# STM32F103_coreboard_2.net
KiCad netlist of a schematic drawn in Altium Designer
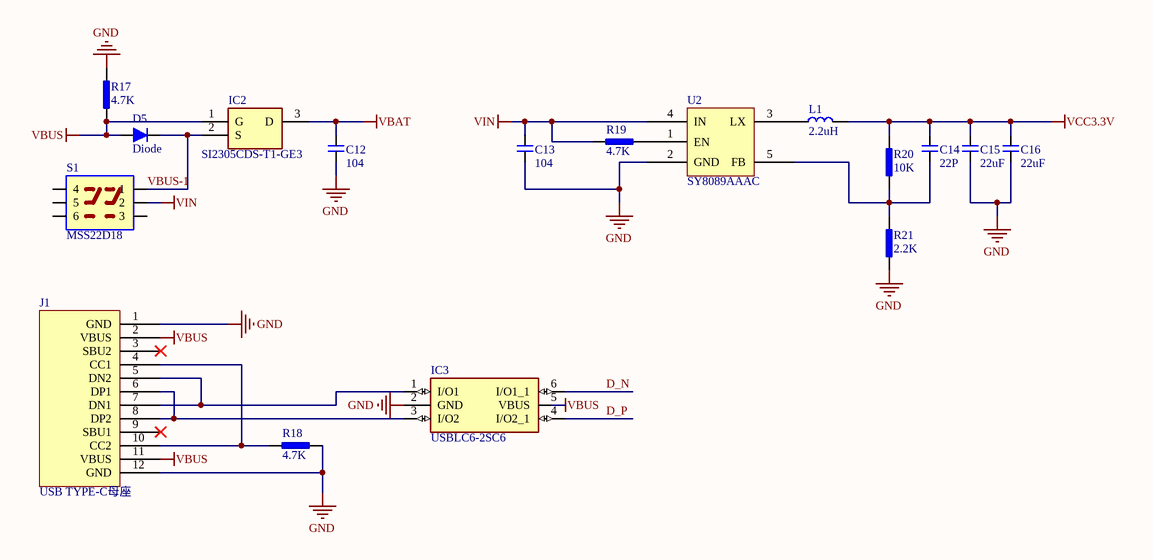
[diagram p0: STM32F103_coreboard_2.SchDoc]

(export (version "E")
  (design (tool "Eeschema 10.0.6"))
  (components
    (comp (ref "C12")
      (value "104")
      (footprint "C0603")
      (description "Cap")
      (libsource (lib "SCH_Bacsic") (part "CAP"))
    )
    (comp (ref "C13")
      (value "104")
      (footprint "C0603")
      (description "Cap")
      (libsource (lib "SCH_Bacsic") (part "CAP"))
    )
    (comp (ref "C14")
      (value "22P")
      (footprint "C0603")
      (description "Cap")
      (libsource (lib "SCH_Bacsic") (part "CAP"))
    )
    (comp (ref "C15")
      (value "22uF")
      (footprint "C0603")
      (description "Cap")
      (libsource (lib "SCH_Bacsic") (part "CAP"))
    )
    (comp (ref "C16")
      (value "22uF")
      (footprint "C0603")
      (description "Cap")
      (libsource (lib "SCH_Bacsic") (part "CAP"))
    )
    (comp (ref "D5") (value "Diode") (footprint "SOD123") (libsource (lib "SCH_Bacsic") (part "Diode")))
    (comp (ref "IC2")
      (value "SI2305CDS-T1-GE3")
      (footprint "SamacSys:SOT95P237X112-3N")
      (description "Integrated Circuit")
      (fields
        (field (name "MOUSER PART NUMBER") "781-SI2305CDS-GE3")
        (field (name "RS PART NUMBER") "7103248P")
      )
      (libsource (lib "*") (part "SI2305CDS-T1-GE3"))
    )
    (comp (ref "IC3")
      (value "USBLC6-2SC6")
      (footprint "SamacSys:SOT95P280X145-6N")
      (description "Integrated Circuit")
      (fields
        (field (name "MOUSER PART NUMBER") "511-USBLC6-2SC6")
        (field (name "RS PART NUMBER") "6247693P")
      )
      (libsource (lib "*") (part "USBLC6-2SC6"))
    )
    (comp (ref "J1")
      (value "USB TYPE-C母座")
      (footprint "USB-TYPEC-SMT")
      (libsource (lib "SCH_Connector") (part "USB TYPE-C"))
    )
    (comp (ref "L1")
      (value "2.2uH")
      (footprint "L-CDR5*5")
      (libsource (lib "SCH_Bacsic") (part "Inductance"))
    )
    (comp (ref "R17") (value "4.7K") (footprint "R0603") (libsource (lib "") (part "RES_2")))
    (comp (ref "R18") (value "4.7K") (footprint "R0603") (libsource (lib "SCH_Bacsic") (part "RES")))
    (comp (ref "R19") (value "4.7K") (footprint "R0603") (libsource (lib "SCH_Bacsic") (part "RES")))
    (comp (ref "R20") (value "10K") (footprint "R0603") (libsource (lib "") (part "RES_1")))
    (comp (ref "R21") (value "2.2K") (footprint "R0603") (libsource (lib "") (part "RES_1")))
    (comp (ref "S1")
      (value "MSS22D18")
      (footprint "SWITCH-MSS22D18")
      (libsource (lib "SCH_Switch_and_Key") (part "SWITCH-MSS22D18"))
    )
    (comp (ref "U2")
      (value "SY8089AAAC")
      (footprint "SOT-23-5")
      (libsource (lib "SCH_Integrated_Circuit") (part "SY8089AAAC"))
    )
  )
  (nets
    (net (code "1") (name "/D_N") (class "Default")
      (node (ref "IC3") (pin "6") (pinfunction "I/O1_1_6") (pintype "bidirectional"))
    )
    (net (code "2") (name "/D_P") (class "Default")
      (node (ref "IC3") (pin "4") (pinfunction "I/O2_1_4") (pintype "bidirectional"))
    )
    (net (code "3") (name "/VBUS-1") (class "Default")
      (node (ref "D5") (pin "2") (pintype "passive"))
      (node (ref "IC2") (pin "2") (pinfunction "S_2") (pintype "passive"))
      (node (ref "S1") (pin "1") (pinfunction "1_1") (pintype "passive"))
    )
    (net (code "4") (name "GND") (class "Default")
      (node (ref "C12") (pin "1") (pintype "passive"))
      (node (ref "C13") (pin "1") (pintype "passive"))
      (node (ref "C15") (pin "1") (pintype "passive"))
      (node (ref "C16") (pin "1") (pintype "passive"))
      (node (ref "IC3") (pin "2") (pinfunction "GND_2") (pintype "power_in"))
      (node (ref "J1") (pin "1") (pinfunction "GND_1") (pintype "passive"))
      (node (ref "J1") (pin "12") (pinfunction "GND_12") (pintype "passive"))
      (node (ref "R17") (pin "1") (pintype "passive"))
      (node (ref "R18") (pin "2") (pintype "passive"))
      (node (ref "R21") (pin "1") (pintype "passive"))
      (node (ref "U2") (pin "2") (pinfunction "GND_2") (pintype "passive"))
    )
    (net (code "5") (name "Net-(IC3-I{slash}O1)") (class "Default")
      (node (ref "IC3") (pin "1") (pinfunction "I/O1_1") (pintype "bidirectional"))
      (node (ref "J1") (pin "5") (pinfunction "DN2_5") (pintype "passive"))
      (node (ref "J1") (pin "7") (pinfunction "DN1_7") (pintype "passive"))
    )
    (net (code "6") (name "Net-(IC3-I{slash}O2)") (class "Default")
      (node (ref "IC3") (pin "3") (pinfunction "I/O2_3") (pintype "bidirectional"))
      (node (ref "J1") (pin "6") (pinfunction "DP1_6") (pintype "passive"))
      (node (ref "J1") (pin "8") (pinfunction "DP2_8") (pintype "passive"))
    )
    (net (code "7") (name "Net-(J1-CC1)") (class "Default")
      (node (ref "J1") (pin "10") (pinfunction "CC2_10") (pintype "passive"))
      (node (ref "J1") (pin "4") (pinfunction "CC1_4") (pintype "passive"))
      (node (ref "R18") (pin "1") (pintype "passive"))
    )
    (net (code "8") (name "Net-(U2-EN)") (class "Default")
      (node (ref "R19") (pin "2") (pintype "passive"))
      (node (ref "U2") (pin "1") (pinfunction "EN_1") (pintype "passive"))
    )
    (net (code "9") (name "Net-(U2-FB)") (class "Default")
      (node (ref "C14") (pin "1") (pintype "passive"))
      (node (ref "R20") (pin "1") (pintype "passive"))
      (node (ref "R21") (pin "2") (pintype "passive"))
      (node (ref "U2") (pin "5") (pinfunction "FB_5") (pintype "passive"))
    )
    (net (code "10") (name "Net-(U2-LX)") (class "Default")
      (node (ref "L1") (pin "2") (pinfunction "2_2") (pintype "passive"))
      (node (ref "U2") (pin "3") (pinfunction "LX_3") (pintype "passive"))
    )
    (net (code "11") (name "VBAT") (class "Default")
      (node (ref "C12") (pin "2") (pintype "passive"))
      (node (ref "IC2") (pin "3") (pinfunction "D_3") (pintype "passive"))
    )
    (net (code "12") (name "VBUS") (class "Default")
      (node (ref "D5") (pin "1") (pintype "passive"))
      (node (ref "IC2") (pin "1") (pinfunction "G_1") (pintype "passive"))
      (node (ref "IC3") (pin "5") (pinfunction "VBUS_5") (pintype "passive"))
      (node (ref "J1") (pin "11") (pinfunction "VBUS_11") (pintype "passive"))
      (node (ref "J1") (pin "2") (pinfunction "VBUS_2") (pintype "passive"))
      (node (ref "R17") (pin "2") (pintype "passive"))
    )
    (net (code "13") (name "VCC3.3V") (class "Default")
      (node (ref "C14") (pin "2") (pintype "passive"))
      (node (ref "C15") (pin "2") (pintype "passive"))
      (node (ref "C16") (pin "2") (pintype "passive"))
      (node (ref "L1") (pin "1") (pinfunction "1_1") (pintype "passive"))
      (node (ref "R20") (pin "2") (pintype "passive"))
    )
    (net (code "14") (name "VIN") (class "Default")
      (node (ref "C13") (pin "2") (pintype "passive"))
      (node (ref "R19") (pin "1") (pintype "passive"))
      (node (ref "S1") (pin "2") (pinfunction "2_2") (pintype "passive"))
      (node (ref "U2") (pin "4") (pinfunction "IN_4") (pintype "passive"))
    )
    (net (code "15") (name "unconnected-(J1-SBU1-Pad9)") (class "Default")
      (node (ref "J1") (pin "9") (pinfunction "SBU1_9") (pintype "passive+no_connect"))
    )
    (net (code "16") (name "unconnected-(J1-SBU2-Pad3)") (class "Default")
      (node (ref "J1") (pin "3") (pinfunction "SBU2_3") (pintype "passive+no_connect"))
    )
    (net (code "17") (name "unconnected-(S1-Pad3)") (class "Default")
      (node (ref "S1") (pin "3") (pinfunction "3_3") (pintype "passive"))
    )
    (net (code "18") (name "unconnected-(S1-Pad4)") (class "Default")
      (node (ref "S1") (pin "4") (pinfunction "4_4") (pintype "passive"))
    )
    (net (code "19") (name "unconnected-(S1-Pad5)") (class "Default")
      (node (ref "S1") (pin "5") (pinfunction "5_5") (pintype "passive"))
    )
    (net (code "20") (name "unconnected-(S1-Pad6)") (class "Default")
      (node (ref "S1") (pin "6") (pinfunction "6_6") (pintype "passive"))
    )
  )
)
